# praline.net
KiCad netlist of a schematic drawn in Altium Designer
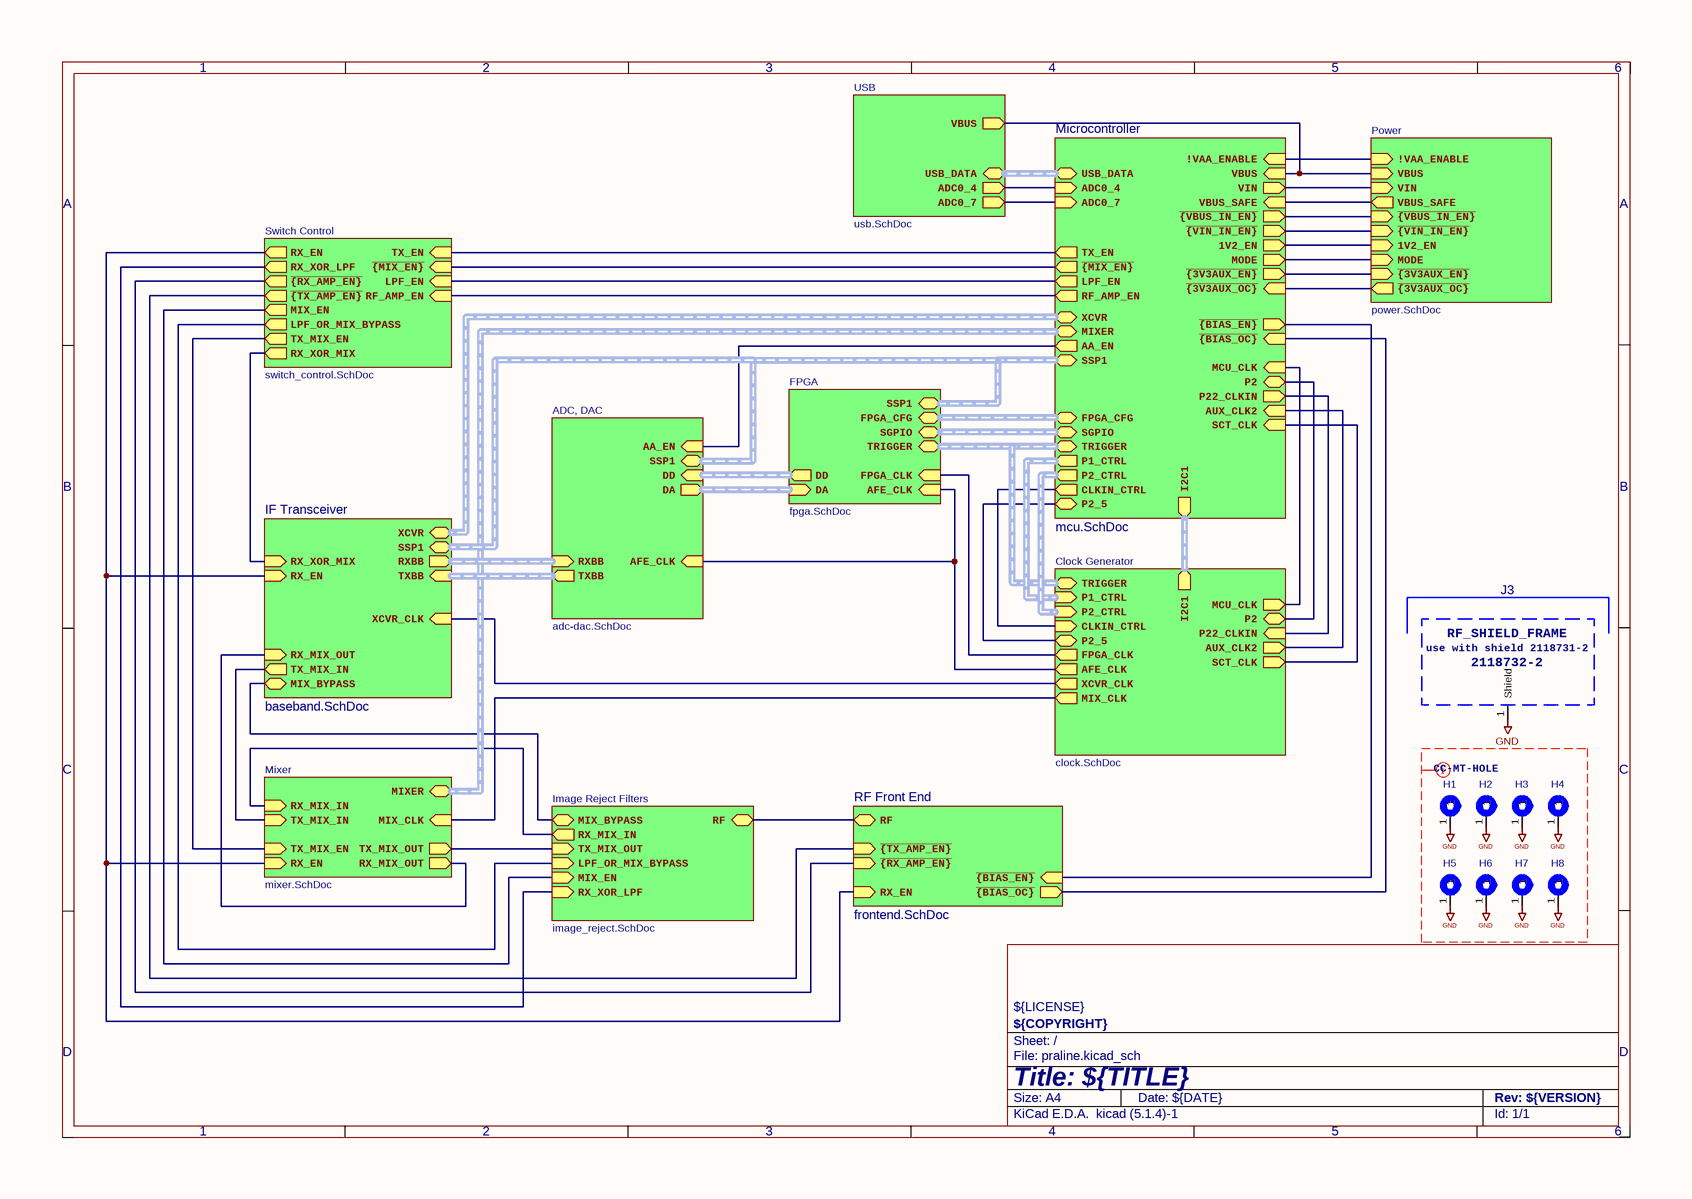
[diagram p0: praline.SchDoc]

(export (version "E")
  (design (tool "Eeschema 10.0.6"))
  (components
    (comp (ref "H1")
      (value "MountingHole_Pad")
      (footprint "MountingHole_3.2mm_M3_Pad_Via")
      (libsource (lib "Mechanical") (part "MountingHole_Pad"))
    )
    (comp (ref "H2")
      (value "MountingHole_Pad")
      (footprint "MountingHole_3.2mm_M3_Pad_Via")
      (libsource (lib "Mechanical") (part "MountingHole_Pad"))
    )
    (comp (ref "H3")
      (value "MountingHole_Pad")
      (footprint "MountingHole_3.2mm_M3_Pad_Via")
      (libsource (lib "Mechanical") (part "MountingHole_Pad"))
    )
    (comp (ref "H4")
      (value "MountingHole_Pad")
      (footprint "MountingHole_3.2mm_M3_Pad_Via")
      (libsource (lib "Mechanical") (part "MountingHole_Pad"))
    )
    (comp (ref "H5")
      (value "MountingHole_Pad")
      (footprint "MountingHole_2.2mm_M2_Pad_Via")
      (libsource (lib "Mechanical") (part "MountingHole_Pad"))
    )
    (comp (ref "H6")
      (value "MountingHole_Pad")
      (footprint "MountingHole_2.2mm_M2_Pad_Via")
      (libsource (lib "Mechanical") (part "MountingHole_Pad"))
    )
    (comp (ref "H7")
      (value "MountingHole_Pad")
      (footprint "MountingHole_2.2mm_M2_Pad_Via")
      (libsource (lib "Mechanical") (part "MountingHole_Pad"))
    )
    (comp (ref "H8")
      (value "MountingHole_Pad")
      (footprint "MountingHole_2.2mm_M2_Pad_Via")
      (libsource (lib "Mechanical") (part "MountingHole_Pad"))
    )
    (comp (ref "J3")
      (value "RF_SHIELD_FRAME")
      (footprint "Laird_Technologies_BMI-S-230-F_50.8x38.1mm")
      (fields
        (field (name "MANUFACTURER") "TE Connectivity")
        (field (name "PART NUMBER") "2118732-2")
        (field (name "NOTE") "use with shield 2118731-2")
      )
      (libsource (lib "Device") (part "RFShield_TwoPieces"))
    )
  )
  (nets
    (net (code "59") (name "GND") (class "Default")
      (node (ref "H1") (pin "1") (pinfunction "1_1") (pintype "passive"))
      (node (ref "H2") (pin "1") (pinfunction "1_1") (pintype "passive"))
      (node (ref "H3") (pin "1") (pinfunction "1_1") (pintype "passive"))
      (node (ref "H4") (pin "1") (pinfunction "1_1") (pintype "passive"))
      (node (ref "H5") (pin "1") (pinfunction "1_1") (pintype "passive"))
      (node (ref "H6") (pin "1") (pinfunction "1_1") (pintype "passive"))
      (node (ref "H7") (pin "1") (pinfunction "1_1") (pintype "passive"))
      (node (ref "H8") (pin "1") (pinfunction "1_1") (pintype "passive"))
      (node (ref "J3") (pin "1") (pinfunction "Shield_1") (pintype "passive"))
    )
  )
)
